# 01_MCU.net
KiCad netlist of a schematic drawn in Altium Designer
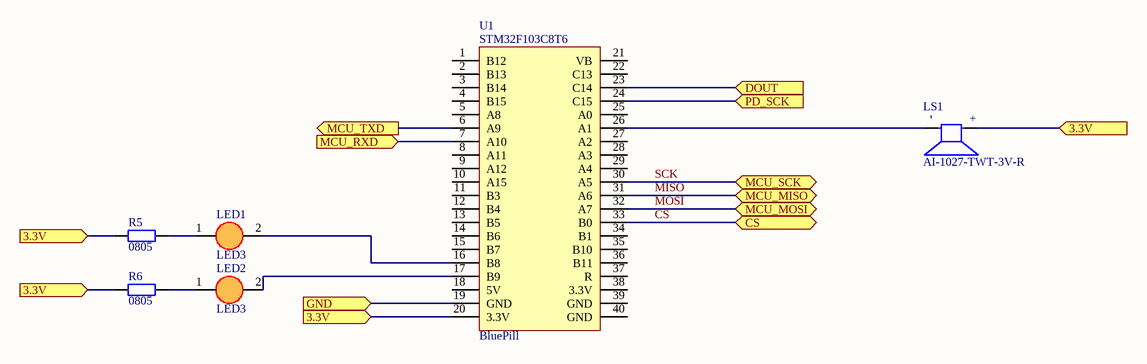
[diagram p0: 01_MCU.SchDoc]

(export (version "E")
  (design (tool "Eeschema 10.0.6"))
  (components
    (comp (ref "LED1")
      (value "LED3")
      (footprint "LED3mm")
      (description "LED 3mm")
      (libsource (lib "My Library") (part "LED 3mm"))
    )
    (comp (ref "LED2")
      (value "LED3")
      (footprint "LED3mm")
      (description "LED 3mm")
      (libsource (lib "My Library") (part "LED 3mm"))
    )
    (comp (ref "LS1")
      (value "AI-1027-TWT-3V-R")
      (footprint "XDCR_AI-1027-TWT-3V-R")
      (fields (field (name "MF") "PUI Audio, Inc."))
      (libsource (lib "AI-1027-TWT-3V-R") (part "AI-1027-TWT-3V-R"))
    )
    (comp (ref "R5")
      (value "0805")
      (footprint "DIEN TRO 0805")
      (description "Resistor SMD 0805")
      (fields (field (name "Comment") "R0805") (field (name "PUBLISHER") "Altium Limited"))
      (libsource (lib "My Library") (part "R0805"))
    )
    (comp (ref "R6")
      (value "0805")
      (footprint "DIEN TRO 0805")
      (description "Resistor SMD 0805")
      (fields (field (name "Comment") "R0805") (field (name "PUBLISHER") "Altium Limited"))
      (libsource (lib "My Library") (part "R0805"))
    )
    (comp (ref "U1")
      (value "BluePill")
      (footprint "DIP40 - duplicate")
      (libsource (lib "Bluepill") (part "BluePill"))
    )
  )
  (nets
    (net (code "1") (name "/3.3V") (class "Default")
      (node (ref "LS1") (pin "P") (pinfunction "P_P") (pintype "passive"))
      (node (ref "R5") (pin "1") (pinfunction "1_1") (pintype "passive"))
      (node (ref "R6") (pin "1") (pinfunction "1_1") (pintype "passive"))
      (node (ref "U1") (pin "20") (pinfunction "3.3V_20") (pintype "passive"))
    )
    (net (code "2") (name "/CS") (class "Default")
      (node (ref "U1") (pin "33") (pinfunction "B0_33") (pintype "passive"))
    )
    (net (code "3") (name "/DOUT") (class "Default")
      (node (ref "U1") (pin "23") (pinfunction "C14_23") (pintype "passive"))
    )
    (net (code "4") (name "/GND") (class "Default")
      (node (ref "U1") (pin "19") (pinfunction "GND_19") (pintype "passive"))
    )
    (net (code "5") (name "/MCU_RXD") (class "Default")
      (node (ref "U1") (pin "7") (pinfunction "A10_7") (pintype "passive"))
    )
    (net (code "6") (name "/MCU_TXD") (class "Default")
      (node (ref "U1") (pin "6") (pinfunction "A9_6") (pintype "passive"))
    )
    (net (code "7") (name "/MISO") (class "Default")
      (node (ref "U1") (pin "31") (pinfunction "A6_31") (pintype "passive"))
    )
    (net (code "8") (name "/MOSI") (class "Default")
      (node (ref "U1") (pin "32") (pinfunction "A7_32") (pintype "passive"))
    )
    (net (code "9") (name "/PD_SCK") (class "Default")
      (node (ref "U1") (pin "24") (pinfunction "C15_24") (pintype "passive"))
    )
    (net (code "10") (name "/SCK") (class "Default")
      (node (ref "U1") (pin "30") (pinfunction "A5_30") (pintype "passive"))
    )
    (net (code "11") (name "Net-(LED1-A)") (class "Default")
      (node (ref "LED1") (pin "1") (pinfunction "A_1") (pintype "passive"))
      (node (ref "R5") (pin "2") (pinfunction "2_2") (pintype "passive"))
    )
    (net (code "12") (name "Net-(LED1-K)") (class "Default")
      (node (ref "LED1") (pin "2") (pinfunction "K_2") (pintype "passive"))
      (node (ref "U1") (pin "16") (pinfunction "B8_16") (pintype "passive"))
    )
    (net (code "13") (name "Net-(LED2-A)") (class "Default")
      (node (ref "LED2") (pin "1") (pinfunction "A_1") (pintype "passive"))
      (node (ref "R6") (pin "2") (pinfunction "2_2") (pintype "passive"))
    )
    (net (code "14") (name "Net-(LED2-K)") (class "Default")
      (node (ref "LED2") (pin "2") (pinfunction "K_2") (pintype "passive"))
      (node (ref "U1") (pin "17") (pinfunction "B9_17") (pintype "passive"))
    )
    (net (code "15") (name "Net-(U1-A1)") (class "Default")
      (node (ref "LS1") (pin "N") (pinfunction "N_N") (pintype "passive"))
      (node (ref "U1") (pin "26") (pinfunction "A1_26") (pintype "passive"))
    )
    (net (code "16") (name "unconnected-(U1-3.3V-Pad38)") (class "Default")
      (node (ref "U1") (pin "38") (pinfunction "3.3V_38") (pintype "passive"))
    )
    (net (code "17") (name "unconnected-(U1-5V-Pad18)") (class "Default")
      (node (ref "U1") (pin "18") (pinfunction "5V_18") (pintype "passive"))
    )
    (net (code "18") (name "unconnected-(U1-A0-Pad25)") (class "Default")
      (node (ref "U1") (pin "25") (pinfunction "A0_25") (pintype "passive"))
    )
    (net (code "19") (name "unconnected-(U1-A2-Pad27)") (class "Default")
      (node (ref "U1") (pin "27") (pinfunction "A2_27") (pintype "passive"))
    )
    (net (code "20") (name "unconnected-(U1-A3-Pad28)") (class "Default")
      (node (ref "U1") (pin "28") (pinfunction "A3_28") (pintype "passive"))
    )
    (net (code "21") (name "unconnected-(U1-A4-Pad29)") (class "Default")
      (node (ref "U1") (pin "29") (pinfunction "A4_29") (pintype "passive"))
    )
    (net (code "22") (name "unconnected-(U1-A8-Pad5)") (class "Default")
      (node (ref "U1") (pin "5") (pinfunction "A8_5") (pintype "passive"))
    )
    (net (code "23") (name "unconnected-(U1-A11-Pad8)") (class "Default")
      (node (ref "U1") (pin "8") (pinfunction "A11_8") (pintype "passive"))
    )
    (net (code "24") (name "unconnected-(U1-A12-Pad9)") (class "Default")
      (node (ref "U1") (pin "9") (pinfunction "A12_9") (pintype "passive"))
    )
    (net (code "25") (name "unconnected-(U1-A15-Pad10)") (class "Default")
      (node (ref "U1") (pin "10") (pinfunction "A15_10") (pintype "passive"))
    )
    (net (code "26") (name "unconnected-(U1-B1-Pad34)") (class "Default")
      (node (ref "U1") (pin "34") (pinfunction "B1_34") (pintype "passive"))
    )
    (net (code "27") (name "unconnected-(U1-B3-Pad11)") (class "Default")
      (node (ref "U1") (pin "11") (pinfunction "B3_11") (pintype "passive"))
    )
    (net (code "28") (name "unconnected-(U1-B4-Pad12)") (class "Default")
      (node (ref "U1") (pin "12") (pinfunction "B4_12") (pintype "passive"))
    )
    (net (code "29") (name "unconnected-(U1-B5-Pad13)") (class "Default")
      (node (ref "U1") (pin "13") (pinfunction "B5_13") (pintype "passive"))
    )
    (net (code "30") (name "unconnected-(U1-B6-Pad14)") (class "Default")
      (node (ref "U1") (pin "14") (pinfunction "B6_14") (pintype "passive"))
    )
    (net (code "31") (name "unconnected-(U1-B7-Pad15)") (class "Default")
      (node (ref "U1") (pin "15") (pinfunction "B7_15") (pintype "passive"))
    )
    (net (code "32") (name "unconnected-(U1-B10-Pad35)") (class "Default")
      (node (ref "U1") (pin "35") (pinfunction "B10_35") (pintype "passive"))
    )
    (net (code "33") (name "unconnected-(U1-B11-Pad36)") (class "Default")
      (node (ref "U1") (pin "36") (pinfunction "B11_36") (pintype "passive"))
    )
    (net (code "34") (name "unconnected-(U1-B12-Pad1)") (class "Default")
      (node (ref "U1") (pin "1") (pinfunction "B12_1") (pintype "passive"))
    )
    (net (code "35") (name "unconnected-(U1-B13-Pad2)") (class "Default")
      (node (ref "U1") (pin "2") (pinfunction "B13_2") (pintype "passive"))
    )
    (net (code "36") (name "unconnected-(U1-B14-Pad3)") (class "Default")
      (node (ref "U1") (pin "3") (pinfunction "B14_3") (pintype "passive"))
    )
    (net (code "37") (name "unconnected-(U1-B15-Pad4)") (class "Default")
      (node (ref "U1") (pin "4") (pinfunction "B15_4") (pintype "passive"))
    )
    (net (code "38") (name "unconnected-(U1-C13-Pad22)") (class "Default")
      (node (ref "U1") (pin "22") (pinfunction "C13_22") (pintype "passive"))
    )
    (net (code "39") (name "unconnected-(U1-GND-Pad39)") (class "Default")
      (node (ref "U1") (pin "39") (pinfunction "GND_39") (pintype "passive"))
    )
    (net (code "40") (name "unconnected-(U1-GND-Pad40)") (class "Default")
      (node (ref "U1") (pin "40") (pinfunction "GND_40") (pintype "passive"))
    )
    (net (code "41") (name "unconnected-(U1-R-Pad37)") (class "Default")
      (node (ref "U1") (pin "37") (pinfunction "R_37") (pintype "passive"))
    )
    (net (code "42") (name "unconnected-(U1-VB-Pad21)") (class "Default")
      (node (ref "U1") (pin "21") (pinfunction "VB_21") (pintype "passive"))
    )
  )
)
